# Peripherals.net
KiCad netlist of a schematic drawn in Altium Designer
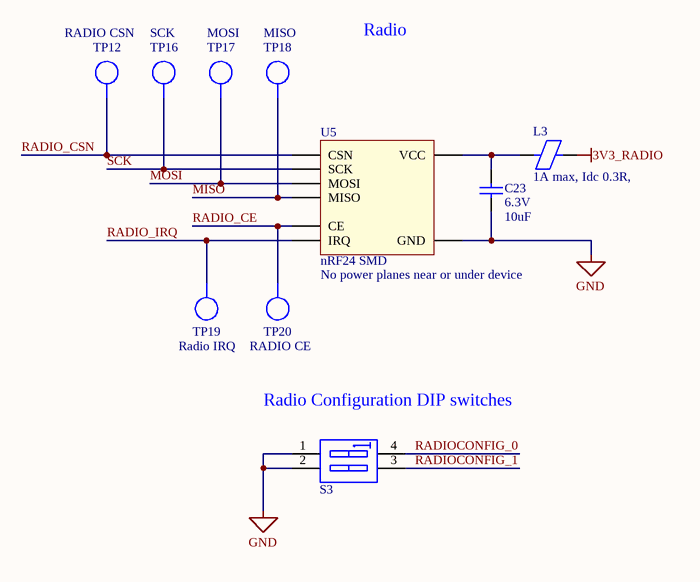
[diagram p0: Peripherals.SchDoc]

(export (version "E")
  (design (tool "Eeschema 10.0.6"))
  (components
    (comp (ref "C23")
      (value "10uF")
      (footprint "CAPC1608L")
      (description "CAP CER 10UF X5R +-20% 6V3 0603")
      (fields (field (name "VOLTAGE - RATED") "6.3V"))
      (libsource (lib "ECE_ComponentsAD23") (part "CC_10uF_0603"))
    )
    (comp (ref "L3")
      (value "1A max, Idc 0.3R,")
      (footprint "INDC3216L")
      (description "Ferrite Bead, Rdc 0.3R, Z100MHZ 600R, Imax 1A, SMD 1206")
      (fields
        (field (name "MANUFACTURER") "FAIR-RITE")
        (field (name "MANUFACTURER PART NUMBER") "2512066017Y1")
      )
      (libsource (lib "ECE_ComponentsAD23") (part "IN_Ferrite-Bead"))
    )
    (comp (ref "S3")
      (value "WS_SW DIP-2")
      (footprint "DIP_SW_2WAY_SMD")
      (description "DIP Switch, 2 Position, SPST SMD")
      (fields
        (field (name "MANUFACTURER") "OMRON ELECTRONIC COMPONENTS")
        (field (name "MANUFACTURER PART NUMBER") "A6SN-2101")
      )
      (libsource (lib "ECE_ComponentsAD23") (part "WS_SW DIP-2"))
    )
    (comp (ref "TP12")
      (value "RADIO CSN")
      (footprint "TP_1206")
      (description "Test-Point 3.3x1.6x2.1mm SMD")
      (fields
        (field (name "MANUFACTURER") "Harwin Inc")
        (field (name "MANUFACTURER PART NUMBER") "S1751-46R")
      )
      (libsource (lib "ECE_ComponentsAD23") (part "TP_1206"))
    )
    (comp (ref "TP16")
      (value "SCK")
      (footprint "TP_1206")
      (description "Test-Point 3.3x1.6x2.1mm SMD")
      (fields
        (field (name "MANUFACTURER") "Harwin Inc")
        (field (name "MANUFACTURER PART NUMBER") "S1751-46R")
      )
      (libsource (lib "ECE_ComponentsAD23") (part "TP_1206"))
    )
    (comp (ref "TP17")
      (value "MOSI")
      (footprint "TP_1206")
      (description "Test-Point 3.3x1.6x2.1mm SMD")
      (fields
        (field (name "MANUFACTURER") "Harwin Inc")
        (field (name "MANUFACTURER PART NUMBER") "S1751-46R")
      )
      (libsource (lib "ECE_ComponentsAD23") (part "TP_1206"))
    )
    (comp (ref "TP18")
      (value "MISO")
      (footprint "TP_1206")
      (description "Test-Point 3.3x1.6x2.1mm SMD")
      (fields
        (field (name "MANUFACTURER") "Harwin Inc")
        (field (name "MANUFACTURER PART NUMBER") "S1751-46R")
      )
      (libsource (lib "ECE_ComponentsAD23") (part "TP_1206"))
    )
    (comp (ref "TP19")
      (value "Radio IRQ")
      (footprint "TP_1206")
      (description "Test-Point 3.3x1.6x2.1mm SMD")
      (fields
        (field (name "MANUFACTURER") "Harwin Inc")
        (field (name "MANUFACTURER PART NUMBER") "S1751-46R")
      )
      (libsource (lib "ECE_ComponentsAD23") (part "TP_1206"))
    )
    (comp (ref "TP20")
      (value "RADIO CE")
      (footprint "TP_1206")
      (description "Test-Point 3.3x1.6x2.1mm SMD")
      (fields
        (field (name "MANUFACTURER") "Harwin Inc")
        (field (name "MANUFACTURER PART NUMBER") "S1751-46R")
      )
      (libsource (lib "ECE_ComponentsAD23") (part "TP_1206"))
    )
    (comp (ref "U5")
      (value "nRF24 SMD")
      (footprint "NRF24")
      (description "nRF24 SMD Module")
      (fields (field (name "WARNING") "No power planes near or under device"))
      (libsource (lib "ENCE461AD23") (part "NRF24"))
    )
  )
  (nets
    (net (code "1") (name "/MISO") (class "Default")
      (node (ref "TP18") (pin "1") (pinfunction "1_1") (pintype "passive"))
      (node (ref "U5") (pin "7") (pinfunction "MISO_7") (pintype "passive"))
    )
    (net (code "2") (name "/MOSI") (class "Default")
      (node (ref "TP17") (pin "1") (pinfunction "1_1") (pintype "passive"))
      (node (ref "U5") (pin "6") (pinfunction "MOSI_6") (pintype "passive"))
    )
    (net (code "3") (name "/RADIOCONFIG_0") (class "Default")
      (node (ref "S3") (pin "4") (pinfunction "B1_4") (pintype "passive"))
    )
    (net (code "4") (name "/RADIOCONFIG_1") (class "Default")
      (node (ref "S3") (pin "3") (pinfunction "B2_3") (pintype "passive"))
    )
    (net (code "5") (name "/RADIO_CE") (class "Default")
      (node (ref "TP20") (pin "1") (pinfunction "1_1") (pintype "passive"))
      (node (ref "U5") (pin "3") (pinfunction "CE_3") (pintype "passive"))
    )
    (net (code "6") (name "/RADIO_CSN") (class "Default")
      (node (ref "TP12") (pin "1") (pinfunction "1_1") (pintype "passive"))
      (node (ref "U5") (pin "4") (pinfunction "CSN_4") (pintype "passive"))
    )
    (net (code "7") (name "/RADIO_IRQ") (class "Default")
      (node (ref "TP19") (pin "1") (pinfunction "1_1") (pintype "passive"))
      (node (ref "U5") (pin "8") (pinfunction "IRQ_8") (pintype "passive"))
    )
    (net (code "8") (name "/SCK") (class "Default")
      (node (ref "TP16") (pin "1") (pinfunction "1_1") (pintype "passive"))
      (node (ref "U5") (pin "5") (pinfunction "SCK_5") (pintype "passive"))
    )
    (net (code "9") (name "3V3_RADIO") (class "Default")
      (node (ref "L3") (pin "2") (pinfunction "2_2") (pintype "passive"))
    )
    (net (code "10") (name "GND") (class "Default")
      (node (ref "C23") (pin "1") (pinfunction "1_1") (pintype "passive"))
      (node (ref "S3") (pin "1") (pinfunction "A1_1") (pintype "passive"))
      (node (ref "S3") (pin "2") (pinfunction "A2_2") (pintype "passive"))
      (node (ref "U5") (pin "2") (pinfunction "GND_2") (pintype "passive"))
    )
    (net (code "11") (name "Net-(U5-VCC)") (class "Default")
      (node (ref "C23") (pin "2") (pinfunction "2_2") (pintype "passive"))
      (node (ref "L3") (pin "1") (pinfunction "1_1") (pintype "passive"))
      (node (ref "U5") (pin "1") (pinfunction "VCC_1") (pintype "passive"))
    )
  )
)
